# AGC_VCA821.net
KiCad netlist of a schematic drawn in Altium Designer
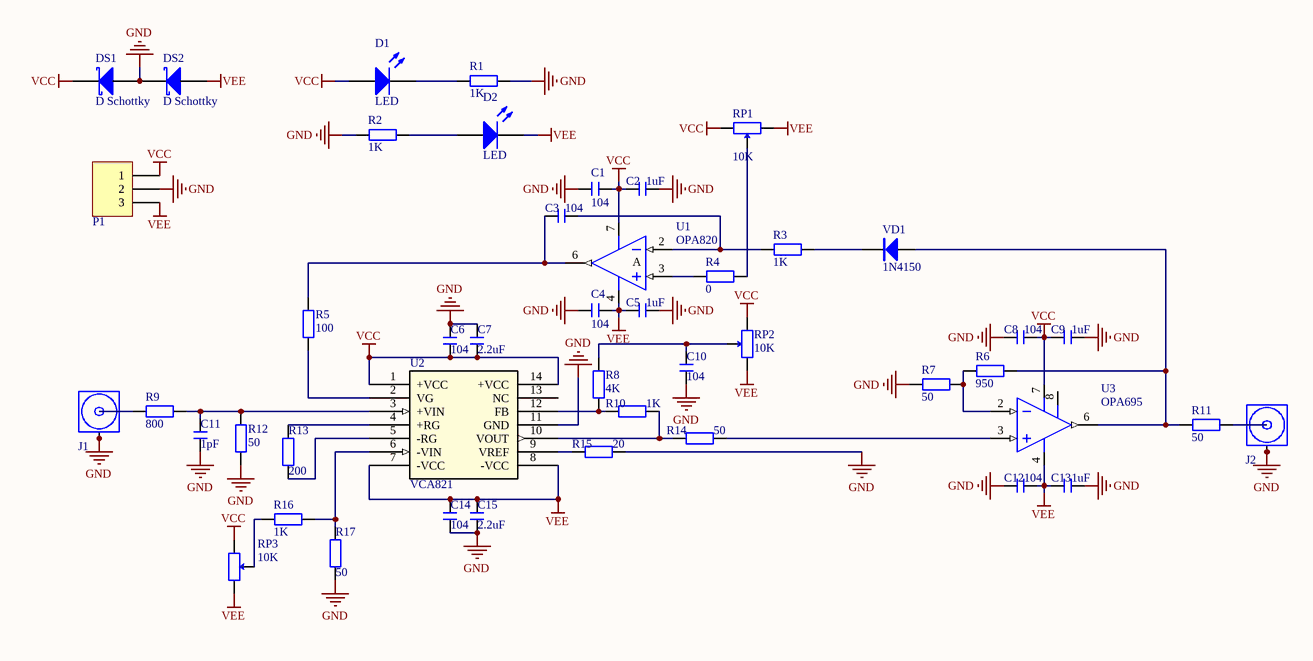
[diagram p0: AGC_VCA821.SchDoc]

(export (version "E")
  (design (tool "Eeschema 10.0.6"))
  (components
    (comp (ref "C1")
      (value "104")
      (footprint "C 0603")
      (description "无极性贴片电容")
      (fields (field (name "版权归属") "源创客"))
      (libsource (lib "电阻-电容-电感") (part "C"))
    )
    (comp (ref "C2")
      (value "1uF")
      (footprint "C 0603")
      (description "无极性贴片电容")
      (fields (field (name "版权归属") "源创客"))
      (libsource (lib "电阻-电容-电感") (part "C"))
    )
    (comp (ref "C3")
      (value "104")
      (footprint "C 0603")
      (description "无极性贴片电容")
      (fields (field (name "版权归属") "源创客"))
      (libsource (lib "电阻-电容-电感") (part "C"))
    )
    (comp (ref "C4")
      (value "104")
      (footprint "C 0603")
      (description "无极性贴片电容")
      (fields (field (name "版权归属") "源创客"))
      (libsource (lib "电阻-电容-电感") (part "C"))
    )
    (comp (ref "C5")
      (value "1uF")
      (footprint "C 0603")
      (description "无极性贴片电容")
      (fields (field (name "版权归属") "源创客"))
      (libsource (lib "电阻-电容-电感") (part "C"))
    )
    (comp (ref "C6")
      (value "104")
      (footprint "C 0603")
      (description "无极性贴片电容")
      (fields (field (name "版权归属") "源创客"))
      (libsource (lib "电阻-电容-电感") (part "C"))
    )
    (comp (ref "C7")
      (value "2.2uF")
      (footprint "C 0603")
      (description "无极性贴片电容")
      (fields (field (name "版权归属") "源创客"))
      (libsource (lib "电阻-电容-电感") (part "C"))
    )
    (comp (ref "C8")
      (value "104")
      (footprint "C 0603")
      (description "无极性贴片电容")
      (fields (field (name "版权归属") "源创客"))
      (libsource (lib "电阻-电容-电感") (part "C"))
    )
    (comp (ref "C9")
      (value "1uF")
      (footprint "C 0603")
      (description "无极性贴片电容")
      (fields (field (name "版权归属") "源创客"))
      (libsource (lib "电阻-电容-电感") (part "C"))
    )
    (comp (ref "C10")
      (value "104")
      (footprint "C 0603")
      (description "无极性贴片电容")
      (fields (field (name "版权归属") "源创客"))
      (libsource (lib "电阻-电容-电感") (part "C"))
    )
    (comp (ref "C11")
      (value "1pF")
      (footprint "C 0603")
      (description "无极性贴片电容")
      (fields (field (name "版权归属") "源创客"))
      (libsource (lib "电阻-电容-电感") (part "C"))
    )
    (comp (ref "C12")
      (value "104")
      (footprint "C 0603")
      (description "无极性贴片电容")
      (fields (field (name "版权归属") "源创客"))
      (libsource (lib "电阻-电容-电感") (part "C"))
    )
    (comp (ref "C13")
      (value "1uF")
      (footprint "C 0603")
      (description "无极性贴片电容")
      (fields (field (name "版权归属") "源创客"))
      (libsource (lib "电阻-电容-电感") (part "C"))
    )
    (comp (ref "C14")
      (value "104")
      (footprint "C 0603")
      (description "无极性贴片电容")
      (fields (field (name "版权归属") "源创客"))
      (libsource (lib "电阻-电容-电感") (part "C"))
    )
    (comp (ref "C15")
      (value "2.2uF")
      (footprint "C 0603")
      (description "无极性贴片电容")
      (fields (field (name "版权归属") "源创客"))
      (libsource (lib "电阻-电容-电感") (part "C"))
    )
    (comp (ref "D1")
      (value "LED")
      (footprint "LED_0805")
      (description "发光二极管")
      (fields (field (name "PUBLISHER") "Altium Limited"))
      (libsource (lib "LIB") (part "LED"))
    )
    (comp (ref "D2")
      (value "LED")
      (footprint "LED_0805")
      (description "发光二极管")
      (fields (field (name "PUBLISHER") "Altium Limited"))
      (libsource (lib "LIB") (part "LED"))
    )
    (comp (ref "DS1")
      (value "D Schottky")
      (footprint "DIODE-SMA")
      (description "Schottky Diode")
      (fields (field (name "PUBLISHER") "Altium Limited"))
      (libsource (lib "LIB") (part "D Schottky"))
    )
    (comp (ref "DS2")
      (value "D Schottky")
      (footprint "DIODE-SMA")
      (description "Schottky Diode")
      (fields (field (name "PUBLISHER") "Altium Limited"))
      (libsource (lib "LIB") (part "D Schottky"))
    )
    (comp (ref "J1") (value "COAX") (footprint "MCX5.08-5-H") (libsource (lib "LIB") (part "COAX")))
    (comp (ref "J2") (value "COAX") (footprint "MCX5.08-5-H") (libsource (lib "LIB") (part "COAX")))
    (comp (ref "P1")
      (value "Header 3")
      (footprint "HDR3X1_B2")
      (description "接插件")
      (fields (field (name "PUBLISHER") "Altium Limited"))
      (libsource (lib "LIB") (part "Header 3"))
    )
    (comp (ref "R1")
      (value "1K")
      (footprint "R 0805")
      (description "贴片电阻")
      (fields (field (name "版权归属") "源创客"))
      (libsource (lib "电阻-电容-电感") (part "R"))
    )
    (comp (ref "R2")
      (value "1K")
      (footprint "R 0805")
      (description "贴片电阻")
      (fields (field (name "版权归属") "源创客"))
      (libsource (lib "电阻-电容-电感") (part "R"))
    )
    (comp (ref "R3")
      (value "1K")
      (footprint "R 0603")
      (description "贴片电阻")
      (fields (field (name "版权归属") "源创客"))
      (libsource (lib "电阻-电容-电感") (part "R"))
    )
    (comp (ref "R4")
      (value "0")
      (footprint "R 0603")
      (description "贴片电阻")
      (fields (field (name "版权归属") "源创客"))
      (libsource (lib "电阻-电容-电感") (part "R"))
    )
    (comp (ref "R5")
      (value "100")
      (footprint "R 0603")
      (description "贴片电阻")
      (fields (field (name "版权归属") "源创客"))
      (libsource (lib "电阻-电容-电感") (part "R"))
    )
    (comp (ref "R6")
      (value "950")
      (footprint "R 0603")
      (description "贴片电阻")
      (fields (field (name "版权归属") "源创客"))
      (libsource (lib "电阻-电容-电感") (part "R"))
    )
    (comp (ref "R7")
      (value "50")
      (footprint "R 0603")
      (description "贴片电阻")
      (fields (field (name "版权归属") "源创客"))
      (libsource (lib "电阻-电容-电感") (part "R"))
    )
    (comp (ref "R8")
      (value "4K")
      (footprint "R 0603")
      (description "贴片电阻")
      (fields (field (name "版权归属") "源创客"))
      (libsource (lib "电阻-电容-电感") (part "R"))
    )
    (comp (ref "R9")
      (value "800")
      (footprint "R 0603")
      (description "贴片电阻")
      (fields (field (name "版权归属") "源创客"))
      (libsource (lib "电阻-电容-电感") (part "R"))
    )
    (comp (ref "R10")
      (value "1K")
      (footprint "R 0603")
      (description "贴片电阻")
      (fields (field (name "版权归属") "源创客"))
      (libsource (lib "电阻-电容-电感") (part "R"))
    )
    (comp (ref "R11")
      (value "50")
      (footprint "R 0603")
      (description "贴片电阻")
      (fields (field (name "版权归属") "源创客"))
      (libsource (lib "电阻-电容-电感") (part "R"))
    )
    (comp (ref "R12")
      (value "50")
      (footprint "R 0603")
      (description "贴片电阻")
      (fields (field (name "版权归属") "源创客"))
      (libsource (lib "电阻-电容-电感") (part "R"))
    )
    (comp (ref "R13")
      (value "200")
      (footprint "R 0603")
      (description "贴片电阻")
      (fields (field (name "版权归属") "源创客"))
      (libsource (lib "电阻-电容-电感") (part "R"))
    )
    (comp (ref "R14")
      (value "50")
      (footprint "R 0603")
      (description "贴片电阻")
      (fields (field (name "版权归属") "源创客"))
      (libsource (lib "电阻-电容-电感") (part "R"))
    )
    (comp (ref "R15")
      (value "20")
      (footprint "R 0603")
      (description "贴片电阻")
      (fields (field (name "版权归属") "源创客"))
      (libsource (lib "电阻-电容-电感") (part "R"))
    )
    (comp (ref "R16")
      (value "1K")
      (footprint "R 0603")
      (description "贴片电阻")
      (fields (field (name "版权归属") "源创客"))
      (libsource (lib "电阻-电容-电感") (part "R"))
    )
    (comp (ref "R17")
      (value "50")
      (footprint "R 0603")
      (description "贴片电阻")
      (fields (field (name "版权归属") "源创客"))
      (libsource (lib "电阻-电容-电感") (part "R"))
    )
    (comp (ref "RP1")
      (value "10K")
      (footprint "3296W")
      (description "插件单联电位器")
      (fields (field (name "版权归属") "源创客"))
      (libsource (lib "电阻-电容-电感") (part "RP-ID"))
    )
    (comp (ref "RP2")
      (value "10K")
      (footprint "3296W")
      (description "插件单联电位器")
      (fields (field (name "版权归属") "源创客"))
      (libsource (lib "电阻-电容-电感") (part "RP-ID"))
    )
    (comp (ref "RP3")
      (value "10K")
      (footprint "3296W")
      (description "插件单联电位器")
      (fields (field (name "版权归属") "源创客"))
      (libsource (lib "电阻-电容-电感") (part "RP-ID"))
    )
    (comp (ref "U1")
      (value "OPA820")
      (footprint "SOIC8_N")
      (description "单位增益稳定低噪声电压反馈运算放大器")
      (libsource (lib "LIB") (part "OPA820"))
    )
    (comp (ref "U2")
      (value "VCA821")
      (footprint "SOIC14_N")
      (description "可变增益放大器 Ultra-Wideband, > 40-dB Gain Adjust Range, Linear in dB")
      (fields
        (field (name "MANUFACTURER") "Texas Instruments")
        (field (name "MANUFACTURER_PART_NUMBER") "vca821_d_14")
      )
      (libsource (lib "LIB") (part "VCA821"))
    )
    (comp (ref "U3")
      (value "OPA695")
      (footprint "SOIC8_N")
      (description "OPA695 Ultra-Wideband, Current-Feedback Operational Amplifier With Disable")
      (libsource (lib "LIB") (part "OPA695"))
    )
    (comp (ref "VD1")
      (value "1N4150")
      (footprint "MINI_MELF (LL34)")
      (description "高速开关二极管")
      (fields (field (name "版权归属") "源创客"))
      (libsource (lib "二极管-整流桥") (part "1N4148"))
    )
  )
  (nets
    (net (code "1") (name "GND") (class "Default")
      (node (ref "C1") (pin "2") (pinfunction "2_2") (pintype "passive"))
      (node (ref "C10") (pin "1") (pinfunction "1_1") (pintype "passive"))
      (node (ref "C11") (pin "1") (pinfunction "1_1") (pintype "passive"))
      (node (ref "C12") (pin "2") (pinfunction "2_2") (pintype "passive"))
      (node (ref "C13") (pin "1") (pinfunction "1_1") (pintype "passive"))
      (node (ref "C14") (pin "2") (pinfunction "2_2") (pintype "passive"))
      (node (ref "C15") (pin "1") (pinfunction "1_1") (pintype "passive"))
      (node (ref "C2") (pin "1") (pinfunction "1_1") (pintype "passive"))
      (node (ref "C4") (pin "2") (pinfunction "2_2") (pintype "passive"))
      (node (ref "C5") (pin "1") (pinfunction "1_1") (pintype "passive"))
      (node (ref "C6") (pin "2") (pinfunction "2_2") (pintype "passive"))
      (node (ref "C7") (pin "2") (pinfunction "2_2") (pintype "passive"))
      (node (ref "C8") (pin "2") (pinfunction "2_2") (pintype "passive"))
      (node (ref "C9") (pin "1") (pinfunction "1_1") (pintype "passive"))
      (node (ref "DS1") (pin "1") (pinfunction "1_1") (pintype "passive"))
      (node (ref "DS2") (pin "2") (pinfunction "2_2") (pintype "passive"))
      (node (ref "J1") (pin "2") (pinfunction "GND_2") (pintype "passive"))
      (node (ref "J1") (pin "3") (pinfunction "GND_3") (pintype "passive"))
      (node (ref "J1") (pin "4") (pinfunction "GND_4") (pintype "passive"))
      (node (ref "J1") (pin "5") (pinfunction "GND_5") (pintype "passive"))
      (node (ref "J2") (pin "2") (pinfunction "GND_2") (pintype "passive"))
      (node (ref "J2") (pin "3") (pinfunction "GND_3") (pintype "passive"))
      (node (ref "J2") (pin "4") (pinfunction "GND_4") (pintype "passive"))
      (node (ref "J2") (pin "5") (pinfunction "GND_5") (pintype "passive"))
      (node (ref "P1") (pin "2") (pinfunction "2_2") (pintype "passive"))
      (node (ref "R1") (pin "2") (pinfunction "2_2") (pintype "passive"))
      (node (ref "R12") (pin "1") (pinfunction "1_1") (pintype "passive"))
      (node (ref "R15") (pin "2") (pinfunction "2_2") (pintype "passive"))
      (node (ref "R17") (pin "1") (pinfunction "1_1") (pintype "passive"))
      (node (ref "R2") (pin "1") (pinfunction "1_1") (pintype "passive"))
      (node (ref "R7") (pin "2") (pinfunction "2_2") (pintype "passive"))
      (node (ref "U2") (pin "11") (pinfunction "GND_11") (pintype "power_in"))
    )
    (net (code "2") (name "Net-(C10-Pad2)") (class "Default")
      (node (ref "C10") (pin "2") (pinfunction "2_2") (pintype "passive"))
      (node (ref "R8") (pin "2") (pinfunction "2_2") (pintype "passive"))
      (node (ref "RP2") (pin "2") (pinfunction "2_2") (pintype "passive"))
    )
    (net (code "3") (name "Net-(D1-K)") (class "Default")
      (node (ref "D1") (pin "2") (pinfunction "K_2") (pintype "passive"))
      (node (ref "R1") (pin "1") (pinfunction "1_1") (pintype "passive"))
    )
    (net (code "4") (name "Net-(D2-A)") (class "Default")
      (node (ref "D2") (pin "1") (pinfunction "A_1") (pintype "passive"))
      (node (ref "R2") (pin "2") (pinfunction "2_2") (pintype "passive"))
    )
    (net (code "5") (name "Net-(J1-Signal)") (class "Default")
      (node (ref "J1") (pin "1") (pinfunction "Signal_1") (pintype "passive"))
      (node (ref "R9") (pin "2") (pinfunction "2_2") (pintype "passive"))
    )
    (net (code "6") (name "Net-(J2-Signal)") (class "Default")
      (node (ref "J2") (pin "1") (pinfunction "Signal_1") (pintype "passive"))
      (node (ref "R11") (pin "1") (pinfunction "1_1") (pintype "passive"))
    )
    (net (code "7") (name "Net-(R4-Pad2)") (class "Default")
      (node (ref "R4") (pin "2") (pinfunction "2_2") (pintype "passive"))
      (node (ref "RP1") (pin "2") (pinfunction "2_2") (pintype "passive"))
    )
    (net (code "8") (name "Net-(R16-Pad2)") (class "Default")
      (node (ref "R16") (pin "2") (pinfunction "2_2") (pintype "passive"))
      (node (ref "RP3") (pin "2") (pinfunction "2_2") (pintype "passive"))
    )
    (net (code "9") (name "Net-(U1-+IN)") (class "Default")
      (node (ref "R4") (pin "1") (pinfunction "1_1") (pintype "passive"))
      (node (ref "U1") (pin "3") (pinfunction "+IN_3") (pintype "input"))
    )
    (net (code "10") (name "Net-(U1--IN)") (class "Default")
      (node (ref "C3") (pin "1") (pinfunction "1_1") (pintype "passive"))
      (node (ref "R3") (pin "2") (pinfunction "2_2") (pintype "passive"))
      (node (ref "U1") (pin "2") (pinfunction "-IN_2") (pintype "input"))
    )
    (net (code "11") (name "Net-(U1-OUT)") (class "Default")
      (node (ref "C3") (pin "2") (pinfunction "2_2") (pintype "passive"))
      (node (ref "R5") (pin "1") (pinfunction "1_1") (pintype "passive"))
      (node (ref "U1") (pin "6") (pinfunction "OUT_6") (pintype "output"))
    )
    (net (code "12") (name "Net-(U2-+RG)") (class "Default")
      (node (ref "R13") (pin "2") (pinfunction "2_2") (pintype "passive"))
      (node (ref "U2") (pin "4") (pinfunction "+RG_4") (pintype "passive"))
    )
    (net (code "13") (name "Net-(U2-+VIN)") (class "Default")
      (node (ref "C11") (pin "2") (pinfunction "2_2") (pintype "passive"))
      (node (ref "R12") (pin "2") (pinfunction "2_2") (pintype "passive"))
      (node (ref "R9") (pin "1") (pinfunction "1_1") (pintype "passive"))
      (node (ref "U2") (pin "3") (pinfunction "+VIN_3") (pintype "input"))
    )
    (net (code "14") (name "Net-(U2--RG)") (class "Default")
      (node (ref "R13") (pin "1") (pinfunction "1_1") (pintype "passive"))
      (node (ref "U2") (pin "5") (pinfunction "-RG_5") (pintype "passive"))
    )
    (net (code "15") (name "Net-(U2--VIN)") (class "Default")
      (node (ref "R16") (pin "1") (pinfunction "1_1") (pintype "passive"))
      (node (ref "R17") (pin "2") (pinfunction "2_2") (pintype "passive"))
      (node (ref "U2") (pin "6") (pinfunction "-VIN_6") (pintype "input"))
    )
    (net (code "16") (name "Net-(U2-FB)") (class "Default")
      (node (ref "R10") (pin "1") (pinfunction "1_1") (pintype "passive"))
      (node (ref "R8") (pin "1") (pinfunction "1_1") (pintype "passive"))
      (node (ref "U2") (pin "12") (pinfunction "FB_12") (pintype "passive"))
    )
    (net (code "17") (name "Net-(U2-VG)") (class "Default")
      (node (ref "R5") (pin "2") (pinfunction "2_2") (pintype "passive"))
      (node (ref "U2") (pin "2") (pinfunction "VG_2") (pintype "passive"))
    )
    (net (code "18") (name "Net-(U2-VOUT)") (class "Default")
      (node (ref "R10") (pin "2") (pinfunction "2_2") (pintype "passive"))
      (node (ref "R14") (pin "1") (pinfunction "1_1") (pintype "passive"))
      (node (ref "U2") (pin "10") (pinfunction "VOUT_10") (pintype "output"))
    )
    (net (code "19") (name "Net-(U2-VREF)") (class "Default")
      (node (ref "R15") (pin "1") (pinfunction "1_1") (pintype "passive"))
      (node (ref "U2") (pin "9") (pinfunction "VREF_9") (pintype "passive"))
    )
    (net (code "20") (name "Net-(U3-IN+)") (class "Default")
      (node (ref "R14") (pin "2") (pinfunction "2_2") (pintype "passive"))
      (node (ref "U3") (pin "3") (pinfunction "IN+_3") (pintype "input"))
    )
    (net (code "21") (name "Net-(U3-IN-)") (class "Default")
      (node (ref "R6") (pin "2") (pinfunction "2_2") (pintype "passive"))
      (node (ref "R7") (pin "1") (pinfunction "1_1") (pintype "passive"))
      (node (ref "U3") (pin "2") (pinfunction "IN-_2") (pintype "input"))
    )
    (net (code "22") (name "Net-(U3-OUT)") (class "Default")
      (node (ref "R11") (pin "2") (pinfunction "2_2") (pintype "passive"))
      (node (ref "R6") (pin "1") (pinfunction "1_1") (pintype "passive"))
      (node (ref "U3") (pin "6") (pinfunction "OUT_6") (pintype "output"))
      (node (ref "VD1") (pin "1") (pinfunction "A_1") (pintype "passive"))
    )
    (net (code "23") (name "Net-(VD1-K)") (class "Default")
      (node (ref "R3") (pin "1") (pinfunction "1_1") (pintype "passive"))
      (node (ref "VD1") (pin "2") (pinfunction "K_2") (pintype "passive"))
    )
    (net (code "24") (name "VCC") (class "Default")
      (node (ref "C1") (pin "1") (pinfunction "1_1") (pintype "passive"))
      (node (ref "C2") (pin "2") (pinfunction "2_2") (pintype "passive"))
      (node (ref "C6") (pin "1") (pinfunction "1_1") (pintype "passive"))
      (node (ref "C7") (pin "1") (pinfunction "1_1") (pintype "passive"))
      (node (ref "C8") (pin "1") (pinfunction "1_1") (pintype "passive"))
      (node (ref "C9") (pin "2") (pinfunction "2_2") (pintype "passive"))
      (node (ref "D1") (pin "1") (pinfunction "A_1") (pintype "passive"))
      (node (ref "DS1") (pin "2") (pinfunction "2_2") (pintype "passive"))
      (node (ref "P1") (pin "1") (pinfunction "1_1") (pintype "passive"))
      (node (ref "RP1") (pin "3") (pinfunction "3_3") (pintype "passive"))
      (node (ref "RP2") (pin "1") (pinfunction "1_1") (pintype "passive"))
      (node (ref "RP3") (pin "3") (pinfunction "3_3") (pintype "passive"))
      (node (ref "U1") (pin "7") (pinfunction "V+_7") (pintype "power_in"))
      (node (ref "U2") (pin "1") (pinfunction "+VCC_1") (pintype "power_in"))
      (node (ref "U2") (pin "14") (pinfunction "+VCC_14") (pintype "power_in"))
      (node (ref "U3") (pin "7") (pinfunction "V+_7") (pintype "power_in"))
    )
    (net (code "25") (name "VEE") (class "Default")
      (node (ref "C12") (pin "1") (pinfunction "1_1") (pintype "passive"))
      (node (ref "C13") (pin "2") (pinfunction "2_2") (pintype "passive"))
      (node (ref "C14") (pin "1") (pinfunction "1_1") (pintype "passive"))
      (node (ref "C15") (pin "2") (pinfunction "2_2") (pintype "passive"))
      (node (ref "C4") (pin "1") (pinfunction "1_1") (pintype "passive"))
      (node (ref "C5") (pin "2") (pinfunction "2_2") (pintype "passive"))
      (node (ref "D2") (pin "2") (pinfunction "K_2") (pintype "passive"))
      (node (ref "DS2") (pin "1") (pinfunction "1_1") (pintype "passive"))
      (node (ref "P1") (pin "3") (pinfunction "3_3") (pintype "passive"))
      (node (ref "RP1") (pin "1") (pinfunction "1_1") (pintype "passive"))
      (node (ref "RP2") (pin "3") (pinfunction "3_3") (pintype "passive"))
      (node (ref "RP3") (pin "1") (pinfunction "1_1") (pintype "passive"))
      (node (ref "U1") (pin "4") (pinfunction "V-_4") (pintype "power_in"))
      (node (ref "U2") (pin "7") (pinfunction "-VCC_7") (pintype "power_in"))
      (node (ref "U2") (pin "8") (pinfunction "-VCC_8") (pintype "power_in"))
      (node (ref "U3") (pin "4") (pinfunction "V-_4") (pintype "power_in"))
    )
    (net (code "26") (name "unconnected-(U2-NC-Pad13)") (class "Default")
      (node (ref "U2") (pin "13") (pinfunction "NC_13") (pintype "passive"))
    )
    (net (code "27") (name "unconnected-(U3-DIS-Pad8)") (class "Default")
      (node (ref "U3") (pin "8") (pinfunction "DIS_8") (pintype "passive"))
    )
  )
)
